# Control.net
KiCad netlist of a schematic drawn in Altium Designer
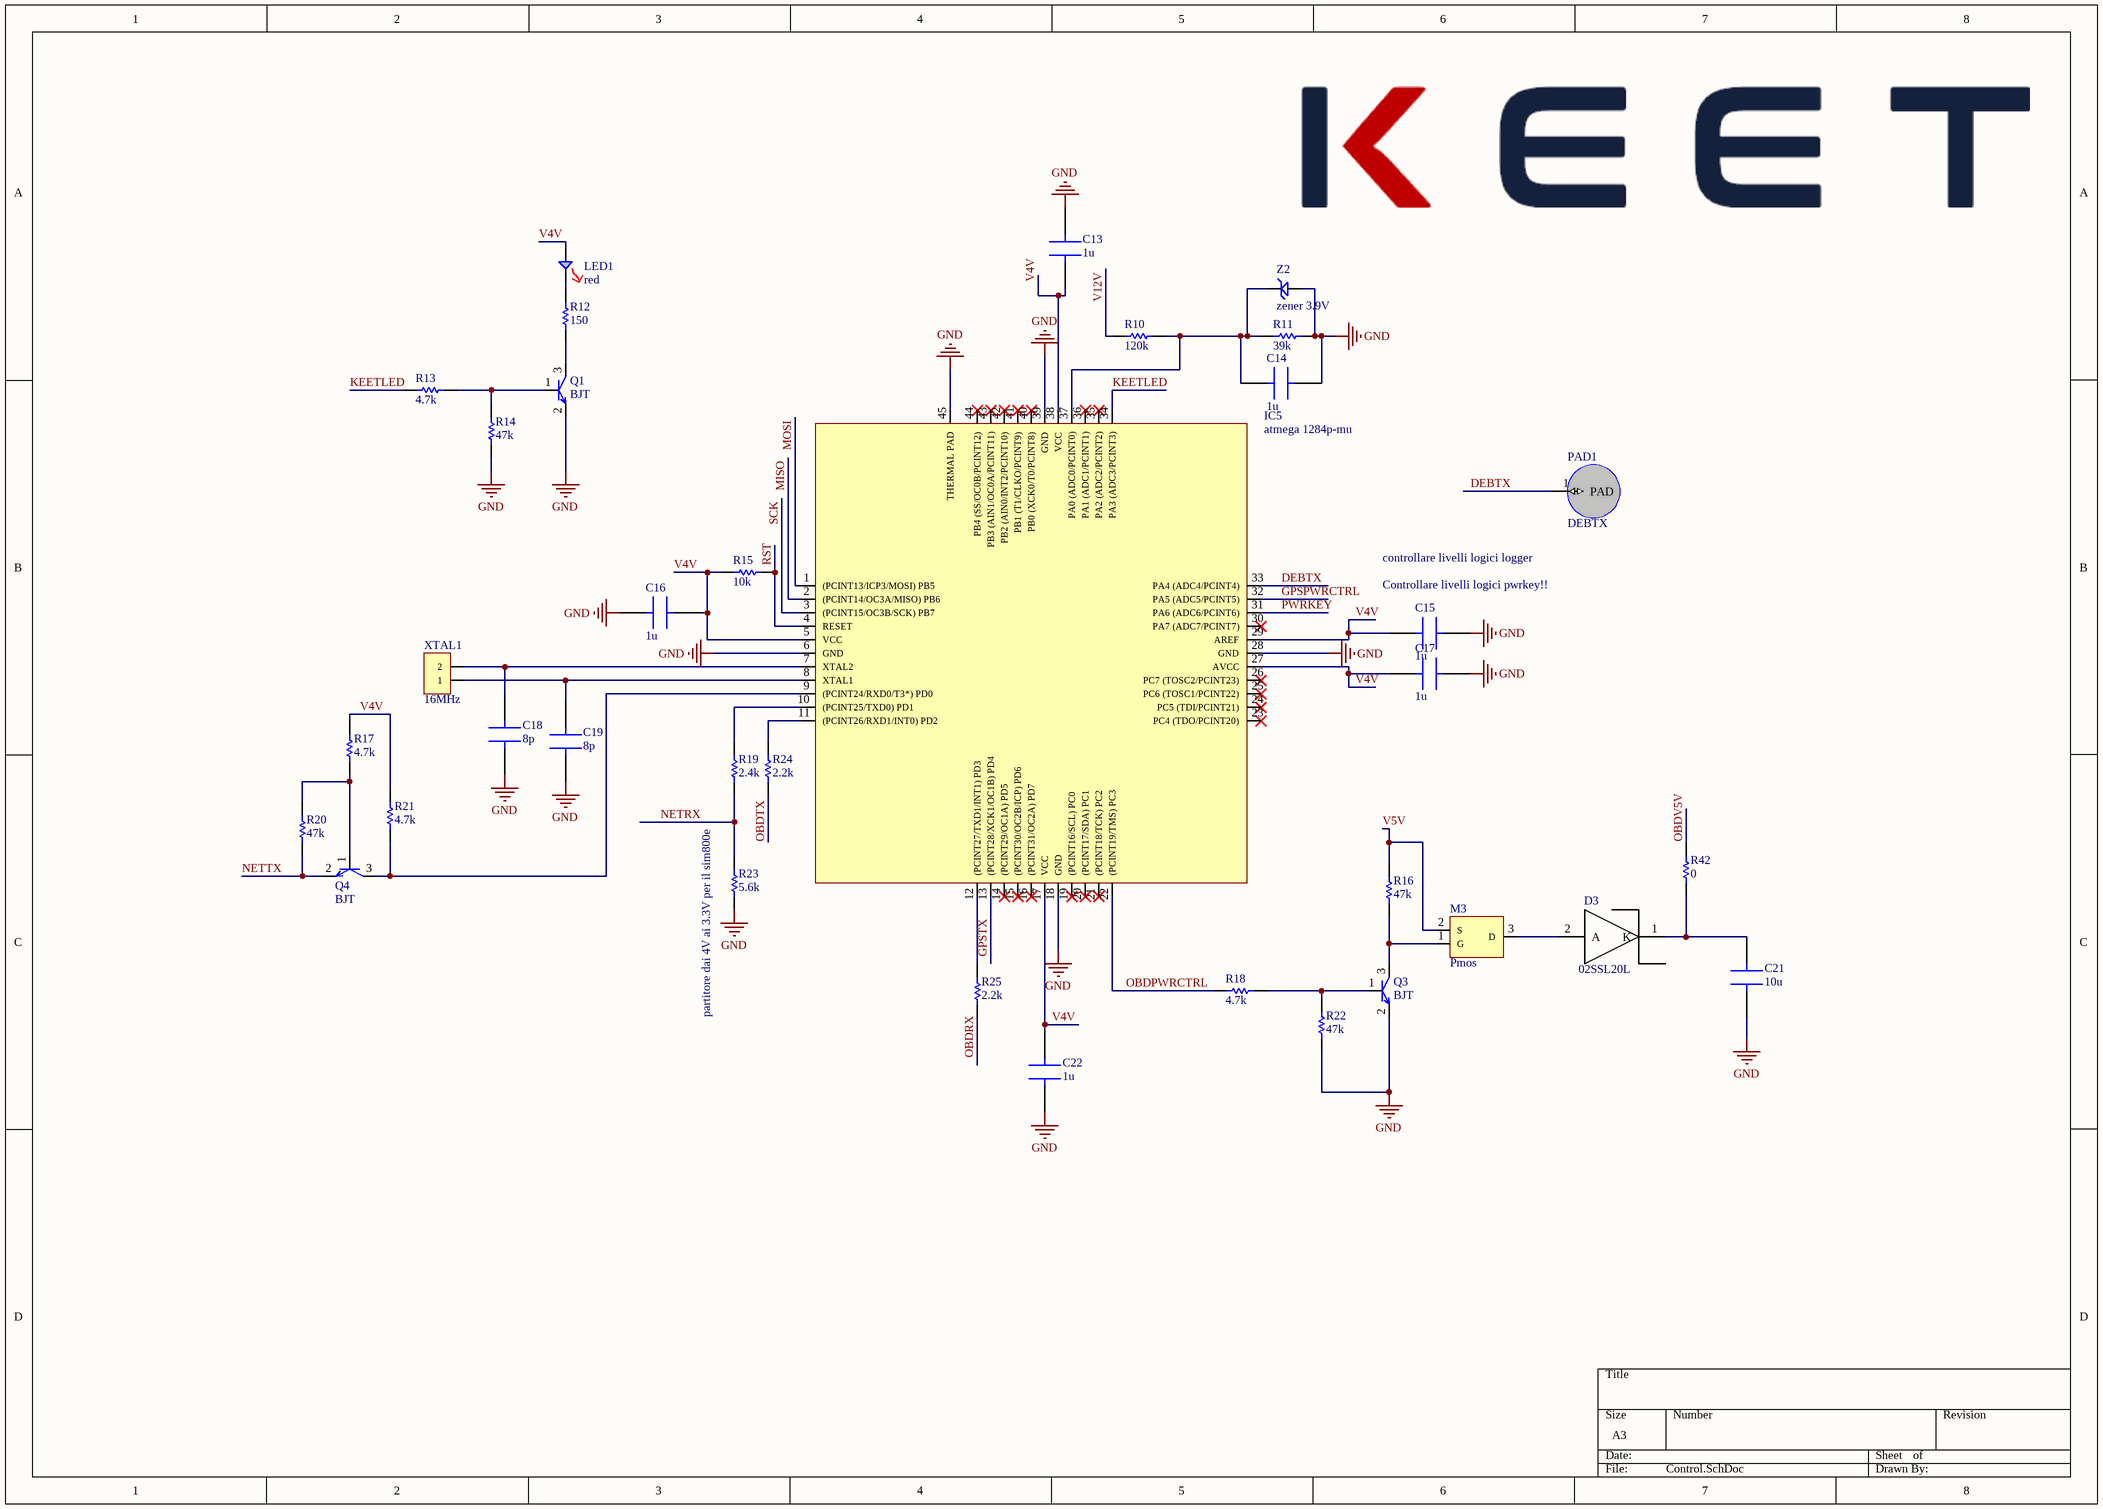
[diagram p0: Control.SchDoc]

(export (version "E")
  (design (tool "Eeschema 10.0.6"))
  (components
    (comp (ref "C13")
      (value "1u")
      (footprint "CAPC1005X06N")
      (description "TAIYO YUDEN - EMK105BJ105KVHF - CAPACITOR,CERAMIC,0402,16V,X5R,1 F, 10% ROHS COMPLIANT: YES")
      (fields
        (field (name "MANUFACTURER") "Taiyo Yuden")
        (field (name "MANUFACTURER PART NUMBER") "EMK105BJ105KVHF")
      )
      (libsource (lib "KeetV2") (part "EMK105BJ105KVHF"))
    )
    (comp (ref "C14")
      (value "1u")
      (footprint "CAPC1005X06N")
      (description "TAIYO YUDEN - EMK105BJ105KVHF - CAPACITOR,CERAMIC,0402,16V,X5R,1 F, 10% ROHS COMPLIANT: YES")
      (fields
        (field (name "MANUFACTURER") "Taiyo Yuden")
        (field (name "MANUFACTURER PART NUMBER") "EMK105BJ105KVHF")
      )
      (libsource (lib "KeetV2") (part "EMK105BJ105KVHF"))
    )
    (comp (ref "C15")
      (value "1u")
      (footprint "CAPC1005X06N")
      (description "TAIYO YUDEN - EMK105BJ105KVHF - CAPACITOR,CERAMIC,0402,16V,X5R,1 F, 10% ROHS COMPLIANT: YES")
      (fields
        (field (name "MANUFACTURER") "Taiyo Yuden")
        (field (name "MANUFACTURER PART NUMBER") "EMK105BJ105KVHF")
      )
      (libsource (lib "KeetV2") (part "EMK105BJ105KVHF"))
    )
    (comp (ref "C16")
      (value "1u")
      (footprint "CAPC1005X06N")
      (description "TAIYO YUDEN - EMK105BJ105KVHF - CAPACITOR,CERAMIC,0402,16V,X5R,1 F, 10% ROHS COMPLIANT: YES")
      (fields
        (field (name "MANUFACTURER") "Taiyo Yuden")
        (field (name "MANUFACTURER PART NUMBER") "EMK105BJ105KVHF")
      )
      (libsource (lib "KeetV2") (part "EMK105BJ105KVHF"))
    )
    (comp (ref "C17")
      (value "1u")
      (footprint "CAPC1005X06N")
      (description "TAIYO YUDEN - EMK105BJ105KVHF - CAPACITOR,CERAMIC,0402,16V,X5R,1 F, 10% ROHS COMPLIANT: YES")
      (fields
        (field (name "MANUFACTURER") "Taiyo Yuden")
        (field (name "MANUFACTURER PART NUMBER") "EMK105BJ105KVHF")
      )
      (libsource (lib "KeetV2") (part "EMK105BJ105KVHF"))
    )
    (comp (ref "C18")
      (value "8p")
      (footprint "CAPC1005X06N")
      (description "Cap Ceramic 8pF 50V C0G 1% SMD 0402 125C Paper T/R")
      (fields
        (field (name "MANUFACTURER") "Murata")
        (field (name "MANUFACTURER PART NUMBER") "GCM1555C1H8R0FA16D")
      )
      (libsource (lib "KeetV2") (part "GCM1555C1H8R0FA16D"))
    )
    (comp (ref "C19")
      (value "8p")
      (footprint "CAPC1005X06N")
      (description "Cap Ceramic 8pF 50V C0G 1% SMD 0402 125C Paper T/R")
      (fields
        (field (name "MANUFACTURER") "Murata")
        (field (name "MANUFACTURER PART NUMBER") "GCM1555C1H8R0FA16D")
      )
      (libsource (lib "KeetV2") (part "GCM1555C1H8R0FA16D"))
    )
    (comp (ref "C21")
      (value "10u")
      (footprint "CAPC1608X10N")
      (fields
        (field (name "MANUFACTURER") "TDK")
        (field (name "MANUFACTURER PART NUMBER") "C1608X5R1A106K080AC")
        (field (name "TOLERANCE") "10%")
      )
      (libsource (lib "KeetV2") (part "C1608X5R1A106K080AC"))
    )
    (comp (ref "C22")
      (value "1u")
      (footprint "CAPC1005X06N")
      (description "TAIYO YUDEN - EMK105BJ105KVHF - CAPACITOR,CERAMIC,0402,16V,X5R,1 F, 10% ROHS COMPLIANT: YES")
      (fields
        (field (name "MANUFACTURER") "Taiyo Yuden")
        (field (name "MANUFACTURER PART NUMBER") "EMK105BJ105KVHF")
      )
      (libsource (lib "KeetV2") (part "EMK105BJ105KVHF"))
    )
    (comp (ref "D3")
      (value "02SSL20L")
      (footprint "SODFL370X100-2N")
      (description "SCHOTTKY DIODE https://eu.mouser.com/datasheet/2/345/02ssl20l-02ssl40l-1107799.pdf")
      (libsource (lib "KeetV2") (part "02SSL20L"))
    )
    (comp (ref "IC5")
      (value "atmega 1284p-mu")
      (footprint "QFN50P700X700X100_HS-45N")
      (description "MCU 8-bit ATmega AVR RISC 128KB Flash 2.5V/3.3V/5V 44-Pin VQFN EP")
      (fields
        (field (name "MANUFACTURER") "Microchip / Atmel")
        (field (name "MANUFACTURER PART NUMBER") "ATMEGA1284P-MU")
      )
      (libsource (lib "KeetV2") (part "ATMEGA1284P-MU"))
    )
    (comp (ref "LED1")
      (value "red")
      (footprint "CAC-0P80X160-2N")
      (description "WURTH ELEKTRONIK - 150060RS75000 - LED, Red, 625 nm, 2 V, 30 mA, 250 mcd RoHS Compliant: Yes")
      (fields
        (field (name "MANUFACTURER") "Wurth Electronics")
        (field (name "MANUFACTURER PART NUMBER") "150060RS75000")
      )
      (libsource (lib "KeetV2") (part "150060RS75000"))
    )
    (comp (ref "M3")
      (value "Pmos")
      (footprint "SOT95P245X110-3N")
      (description "P-Channel 12 V 31 mOhm Surface Mount Enhancement Mode Mosfet - SOT-23-3")
      (fields (field (name "MANUFACTURER") "Diodes") (field (name "MANUFACTURER PART NUMBER") "DMP1045U-7"))
      (libsource (lib "KeetV2") (part "DMP1045U-7"))
    )
    (comp (ref "PAD1")
      (value "DEBTX")
      (footprint "PAD")
      (description "just a pad")
      (libsource (lib "Schlib1") (part "PAD"))
    )
    (comp (ref "Q1")
      (value "BJT")
      (footprint "SOT95P245X110-3N")
      (description "ON SEMICONDUCTOR   BC850CLT1G   BIPOLAR TRANSISTOR, NPN, 45V SOT-23")
      (fields
        (field (name "MANUFACTURER") "ON Semiconductor")
        (field (name "MANUFACTURER PART NUMBER") "BC850CLT1G")
      )
      (libsource (lib "KeetV2") (part "BC850CLT1G"))
    )
    (comp (ref "Q3")
      (value "BJT")
      (footprint "SOT95P245X110-3N")
      (description "ON SEMICONDUCTOR   BC850CLT1G   BIPOLAR TRANSISTOR, NPN, 45V SOT-23")
      (fields
        (field (name "MANUFACTURER") "ON Semiconductor")
        (field (name "MANUFACTURER PART NUMBER") "BC850CLT1G")
      )
      (libsource (lib "KeetV2") (part "BC850CLT1G"))
    )
    (comp (ref "Q4")
      (value "BJT")
      (footprint "SOT95P245X110-3N")
      (description "ON SEMICONDUCTOR   BC850CLT1G   BIPOLAR TRANSISTOR, NPN, 45V SOT-23")
      (fields
        (field (name "MANUFACTURER") "ON Semiconductor")
        (field (name "MANUFACTURER PART NUMBER") "BC850CLT1G")
      )
      (libsource (lib "KeetV2") (part "BC850CLT1G"))
    )
    (comp (ref "R10")
      (value "120k")
      (footprint "RESC1005X04N")
      (description "Res Thick Film 0402 120K Ohm 0.5% 0.063W(1/16W) ±100ppm/C Molded SMD Automotive Punched T/R")
      (fields
        (field (name "MANUFACTURER") "Panasonic")
        (field (name "MANUFACTURER PART NUMBER") "ERJ2RKD1203X")
      )
      (libsource (lib "KeetV2") (part "ERJ2RKD1203X"))
    )
    (comp (ref "R11")
      (value "39k")
      (footprint "RESC1005X04N")
      (description "Res Thick Film 0402 39K Ohm 0.5% 0.063W(1/16W) ±50ppm/C Molded SMD Automotive Punched T/R")
      (fields
        (field (name "MANUFACTURER") "Panasonic")
        (field (name "MANUFACTURER PART NUMBER") "ERJ2RHD3902X")
      )
      (libsource (lib "KeetV2") (part "ERJ2RHD3902X"))
    )
    (comp (ref "R12")
      (value "150")
      (footprint "RESC1005X04N")
      (description "RES SMD 150 OHM 1% 1/10W 0402")
      (fields
        (field (name "MANUFACTURER") "Panasonic")
        (field (name "MANUFACTURER PART NUMBER") "ERJ-2RKF1500X")
      )
      (libsource (lib "KeetV2") (part "ERJ-2RKF1500X"))
    )
    (comp (ref "R13")
      (value "4.7k")
      (footprint "RESC1005X04N")
      (description "Res Thick Film 0402 4.7K Ohm 1% 1/10W Â±100ppm/Â°C Molded SMD SMD Punched Carrier T/R")
      (fields
        (field (name "MANUFACTURER") "Panasonic")
        (field (name "MANUFACTURER PART NUMBER") "ERJ-2RKF4701X")
      )
      (libsource (lib "KeetV2") (part "ERJ-2RKF4701X"))
    )
    (comp (ref "R14")
      (value "47k")
      (footprint "RESC1005X04N")
      (description "Resistor;  Thick Film;  47 Kilohms;  0.063 W;  1%;  SMT;  0402;  TCR 37 ppm/DegC")
      (fields
        (field (name "MANUFACTURER") "Vishay")
        (field (name "MANUFACTURER PART NUMBER") "CRCW040247K0FKED")
      )
      (libsource (lib "KeetV2") (part "CRCW040247K0FKED"))
    )
    (comp (ref "R15")
      (value "10k")
      (footprint "RESC1005X04N")
      (description "Res Thick Film 0402 10K Ohm 1% 1/16W ±100ppm/°C Molded SMD Paper T/R")
      (fields
        (field (name "MANUFACTURER") "Vishay")
        (field (name "MANUFACTURER PART NUMBER") "CRCW0402-10K0FKED")
      )
      (libsource (lib "KeetV2") (part "CRCW0402-10K0FKED"))
    )
    (comp (ref "R16")
      (value "47k")
      (footprint "RESC1005X04N")
      (description "Resistor;  Thick Film;  47 Kilohms;  0.063 W;  1%;  SMT;  0402;  TCR 37 ppm/DegC")
      (fields
        (field (name "MANUFACTURER") "Vishay")
        (field (name "MANUFACTURER PART NUMBER") "CRCW040247K0FKED")
      )
      (libsource (lib "KeetV2") (part "CRCW040247K0FKED"))
    )
    (comp (ref "R17")
      (value "4.7k")
      (footprint "RESC1005X04N")
      (description "Res Thick Film 0402 4.7K Ohm 1% 1/10W Â±100ppm/Â°C Molded SMD SMD Punched Carrier T/R")
      (fields
        (field (name "MANUFACTURER") "Panasonic")
        (field (name "MANUFACTURER PART NUMBER") "ERJ-2RKF4701X")
      )
      (libsource (lib "KeetV2") (part "ERJ-2RKF4701X"))
    )
    (comp (ref "R18")
      (value "4.7k")
      (footprint "RESC1005X04N")
      (description "Res Thick Film 0402 4.7K Ohm 1% 1/10W Â±100ppm/Â°C Molded SMD SMD Punched Carrier T/R")
      (fields
        (field (name "MANUFACTURER") "Panasonic")
        (field (name "MANUFACTURER PART NUMBER") "ERJ-2RKF4701X")
      )
      (libsource (lib "KeetV2") (part "ERJ-2RKF4701X"))
    )
    (comp (ref "R19")
      (value "2.4k")
      (footprint "RESC1005X04N")
      (description "Res Thick Film 0402 2.4K Ohm 1% 0.063W(1/16W) ±100ppm/C Epoxy Pad SMD T/R")
      (fields
        (field (name "MANUFACTURER") "Yageo")
        (field (name "MANUFACTURER PART NUMBER") "RC0402FR-072K4L")
      )
      (libsource (lib "KeetV2") (part "RC0402FR-072K4L"))
    )
    (comp (ref "R20")
      (value "47k")
      (footprint "RESC1005X04N")
      (description "Resistor;  Thick Film;  47 Kilohms;  0.063 W;  1%;  SMT;  0402;  TCR 37 ppm/DegC")
      (fields
        (field (name "MANUFACTURER") "Vishay")
        (field (name "MANUFACTURER PART NUMBER") "CRCW040247K0FKED")
      )
      (libsource (lib "KeetV2") (part "CRCW040247K0FKED"))
    )
    (comp (ref "R21")
      (value "4.7k")
      (footprint "RESC1005X04N")
      (description "Res Thick Film 0402 4.7K Ohm 1% 1/10W Â±100ppm/Â°C Molded SMD SMD Punched Carrier T/R")
      (fields
        (field (name "MANUFACTURER") "Panasonic")
        (field (name "MANUFACTURER PART NUMBER") "ERJ-2RKF4701X")
      )
      (libsource (lib "KeetV2") (part "ERJ-2RKF4701X"))
    )
    (comp (ref "R22")
      (value "47k")
      (footprint "RESC1005X04N")
      (description "Resistor;  Thick Film;  47 Kilohms;  0.063 W;  1%;  SMT;  0402;  TCR 37 ppm/DegC")
      (fields
        (field (name "MANUFACTURER") "Vishay")
        (field (name "MANUFACTURER PART NUMBER") "CRCW040247K0FKED")
      )
      (libsource (lib "KeetV2") (part "CRCW040247K0FKED"))
    )
    (comp (ref "R23")
      (value "5.6k")
      (footprint "RESC1005X04N")
      (description "TE Connectivity CRG0402 Series Thick Film Surface Mount Resistor 0402 Case 5.6k 1% 0.063W 100ppm/C")
      (fields
        (field (name "MANUFACTURER") "TE Connectivity")
        (field (name "MANUFACTURER PART NUMBER") "CRG0402F5K6")
      )
      (libsource (lib "KeetV2") (part "CRG0402F5K6"))
    )
    (comp (ref "R24")
      (value "2.2k")
      (footprint "RESC1005X04N")
      (description "Thick Film Resistors - SMD 2.2K OHM 1%")
      (fields
        (field (name "MANUFACTURER") "Yageo")
        (field (name "MANUFACTURER PART NUMBER") "RC0402FR-132K2L")
      )
      (libsource (lib "KeetV2") (part "RC0402FR-132K2L"))
    )
    (comp (ref "R25")
      (value "2.2k")
      (footprint "RESC1005X04N")
      (description "Thick Film Resistors - SMD 2.2K OHM 1%")
      (fields
        (field (name "MANUFACTURER") "Yageo")
        (field (name "MANUFACTURER PART NUMBER") "RC0402FR-132K2L")
      )
      (libsource (lib "KeetV2") (part "RC0402FR-132K2L"))
    )
    (comp (ref "R42")
      (value "0")
      (footprint "RESC1608X04N")
      (description "YAGEO - RC0603JR-130RL - RES, THICK FILM, 0R, 0.1W, 0603")
      (fields
        (field (name "MANUFACTURER") "Yageo")
        (field (name "MANUFACTURER PART NUMBER") "RC0603JR-130RL")
      )
      (libsource (lib "KeetV2") (part "RC0603JR-130RL"))
    )
    (comp (ref "XTAL1")
      (value "16MHz")
      (footprint "DFN145P200X80-2N")
      (description "Crystal 16MHz ±100ppm (Tol) ±100ppm (Stability) 8pF 100Ohm Automotive 2-Pin SMD T/R")
      (fields
        (field (name "MANUFACTURER") "Murata")
        (field (name "MANUFACTURER PART NUMBER") "XRCHA16M000F0A12R0")
      )
      (libsource (lib "KeetV2") (part "XRCHA16M000F0A12R0"))
    )
    (comp (ref "Z2")
      (value "zener 3.9V")
      (footprint "SODFL250X100-2N")
      (description "ON SEMICONDUCTOR - MM3Z3V9ST1G - Zener Single Diode, 3.9 V, 300 mW, SOD-323, 5 %, 2 Pins, 150 °C")
      (fields
        (field (name "MANUFACTURER") "ON Semiconductor")
        (field (name "MANUFACTURER PART NUMBER") "MM3Z3V9ST1G")
      )
      (libsource (lib "KeetV2") (part "MM3Z3V9ST1G"))
    )
  )
  (nets
    (net (code "1") (name "/DEBTX") (class "Default")
      (node (ref "IC5") (pin "33") (pinfunction "PA4_(ADC4/PCINT4)_33") (pintype "passive"))
      (node (ref "PAD1") (pin "1") (pinfunction "PAD_1") (pintype "bidirectional"))
    )
    (net (code "2") (name "/GPSPWRCTRL") (class "Default")
      (node (ref "IC5") (pin "32") (pinfunction "PA5_(ADC5/PCINT5)_32") (pintype "passive"))
    )
    (net (code "3") (name "/GPSTX") (class "Default")
      (node (ref "IC5") (pin "13") (pinfunction "(PCINT28/XCK1/OC1B)_PD4_13") (pintype "passive"))
    )
    (net (code "4") (name "/KEETLED") (class "Default")
      (node (ref "IC5") (pin "34") (pinfunction "PA3_(ADC3/PCINT3)_34") (pintype "passive"))
      (node (ref "R13") (pin "1") (pinfunction "1_1") (pintype "passive"))
    )
    (net (code "5") (name "/MISO") (class "Default")
      (node (ref "IC5") (pin "2") (pinfunction "(PCINT14/OC3A/MISO)_PB6_2") (pintype "passive"))
    )
    (net (code "6") (name "/MOSI") (class "Default")
      (node (ref "IC5") (pin "1") (pinfunction "(PCINT13/ICP3/MOSI)_PB5_1") (pintype "passive"))
    )
    (net (code "7") (name "/NETRX") (class "Default")
      (node (ref "R19") (pin "1") (pinfunction "1_1") (pintype "passive"))
      (node (ref "R23") (pin "2") (pinfunction "2_2") (pintype "passive"))
    )
    (net (code "8") (name "/NETTX") (class "Default")
      (node (ref "Q4") (pin "2") (pinfunction "2_2") (pintype "passive"))
      (node (ref "R20") (pin "1") (pinfunction "1_1") (pintype "passive"))
    )
    (net (code "9") (name "/OBDPWRCTRL") (class "Default")
      (node (ref "IC5") (pin "22") (pinfunction "(PCINT19/TMS)_PC3_22") (pintype "passive"))
      (node (ref "R18") (pin "1") (pinfunction "1_1") (pintype "passive"))
    )
    (net (code "10") (name "/OBDRX") (class "Default")
      (node (ref "R25") (pin "1") (pinfunction "1_1") (pintype "passive"))
    )
    (net (code "11") (name "/OBDTX") (class "Default")
      (node (ref "R24") (pin "1") (pinfunction "1_1") (pintype "passive"))
    )
    (net (code "12") (name "/OBDV5V") (class "Default")
      (node (ref "R42") (pin "2") (pinfunction "2_2") (pintype "passive"))
    )
    (net (code "13") (name "/PWRKEY") (class "Default")
      (node (ref "IC5") (pin "31") (pinfunction "PA6_(ADC6/PCINT6)_31") (pintype "passive"))
    )
    (net (code "14") (name "/RST") (class "Default")
      (node (ref "IC5") (pin "4") (pinfunction "RESET_4") (pintype "passive"))
      (node (ref "R15") (pin "2") (pinfunction "2_2") (pintype "passive"))
    )
    (net (code "15") (name "/SCK") (class "Default")
      (node (ref "IC5") (pin "3") (pinfunction "(PCINT15/OC3B/SCK)_PB7_3") (pintype "passive"))
    )
    (net (code "16") (name "/V4V") (class "Default")
      (node (ref "C13") (pin "1") (pinfunction "1_1") (pintype "passive"))
      (node (ref "C15") (pin "1") (pinfunction "1_1") (pintype "passive"))
      (node (ref "C16") (pin "2") (pinfunction "2_2") (pintype "passive"))
      (node (ref "C17") (pin "1") (pinfunction "1_1") (pintype "passive"))
      (node (ref "C22") (pin "2") (pinfunction "2_2") (pintype "passive"))
      (node (ref "IC5") (pin "17") (pinfunction "VCC_17") (pintype "passive"))
      (node (ref "IC5") (pin "27") (pinfunction "AVCC_27") (pintype "passive"))
      (node (ref "IC5") (pin "29") (pinfunction "AREF_29") (pintype "passive"))
      (node (ref "IC5") (pin "38") (pinfunction "VCC_38") (pintype "passive"))
      (node (ref "IC5") (pin "5") (pinfunction "VCC_5") (pintype "passive"))
      (node (ref "LED1") (pin "2") (pinfunction "2_2") (pintype "passive"))
      (node (ref "R15") (pin "1") (pinfunction "1_1") (pintype "passive"))
      (node (ref "R17") (pin "2") (pinfunction "2_2") (pintype "passive"))
      (node (ref "R21") (pin "2") (pinfunction "2_2") (pintype "passive"))
    )
    (net (code "17") (name "/V5V") (class "Default")
      (node (ref "M3") (pin "2") (pinfunction "S_2") (pintype "passive"))
      (node (ref "R16") (pin "2") (pinfunction "2_2") (pintype "passive"))
    )
    (net (code "18") (name "/V12V") (class "Default")
      (node (ref "R10") (pin "1") (pinfunction "1_1") (pintype "passive"))
    )
    (net (code "19") (name "GND") (class "Default")
      (node (ref "C13") (pin "2") (pinfunction "2_2") (pintype "passive"))
      (node (ref "C14") (pin "2") (pinfunction "2_2") (pintype "passive"))
      (node (ref "C15") (pin "2") (pinfunction "2_2") (pintype "passive"))
      (node (ref "C16") (pin "1") (pinfunction "1_1") (pintype "passive"))
      (node (ref "C17") (pin "2") (pinfunction "2_2") (pintype "passive"))
      (node (ref "C18") (pin "1") (pinfunction "1_1") (pintype "passive"))
      (node (ref "C19") (pin "1") (pinfunction "1_1") (pintype "passive"))
      (node (ref "C21") (pin "1") (pinfunction "1_1") (pintype "passive"))
      (node (ref "C22") (pin "1") (pinfunction "1_1") (pintype "passive"))
      (node (ref "IC5") (pin "18") (pinfunction "GND_18") (pintype "passive"))
      (node (ref "IC5") (pin "28") (pinfunction "GND_28") (pintype "passive"))
      (node (ref "IC5") (pin "39") (pinfunction "GND_39") (pintype "passive"))
      (node (ref "IC5") (pin "45") (pinfunction "THERMAL_PAD_45") (pintype "passive"))
      (node (ref "IC5") (pin "6") (pinfunction "GND_6") (pintype "passive"))
      (node (ref "Q1") (pin "2") (pinfunction "2_2") (pintype "passive"))
      (node (ref "Q3") (pin "2") (pinfunction "2_2") (pintype "passive"))
      (node (ref "R11") (pin "2") (pinfunction "2_2") (pintype "passive"))
      (node (ref "R14") (pin "1") (pinfunction "1_1") (pintype "passive"))
      (node (ref "R22") (pin "1") (pinfunction "1_1") (pintype "passive"))
      (node (ref "R23") (pin "1") (pinfunction "1_1") (pintype "passive"))
      (node (ref "Z2") (pin "2") (pinfunction "2_2") (pintype "passive"))
    )
    (net (code "20") (name "Net-(D3-A)") (class "Default")
      (node (ref "D3") (pin "2") (pinfunction "A_2") (pintype "passive"))
      (node (ref "M3") (pin "3") (pinfunction "D_3") (pintype "passive"))
    )
    (net (code "21") (name "Net-(D3-K)") (class "Default")
      (node (ref "C21") (pin "2") (pinfunction "2_2") (pintype "passive"))
      (node (ref "D3") (pin "1") (pinfunction "K_1") (pintype "passive"))
      (node (ref "R42") (pin "1") (pinfunction "1_1") (pintype "passive"))
    )
    (net (code "22") (name "Net-(IC5-(PCINT24{slash}RXD0{slash}T3*)_PD0)") (class "Default")
      (node (ref "IC5") (pin "9") (pinfunction "(PCINT24/RXD0/T3*)_PD0_9") (pintype "passive"))
      (node (ref "Q4") (pin "3") (pinfunction "3_3") (pintype "passive"))
      (node (ref "R21") (pin "1") (pinfunction "1_1") (pintype "passive"))
    )
    (net (code "23") (name "Net-(IC5-(PCINT25{slash}TXD0)_PD1)") (class "Default")
      (node (ref "IC5") (pin "10") (pinfunction "(PCINT25/TXD0)_PD1_10") (pintype "passive"))
      (node (ref "R19") (pin "2") (pinfunction "2_2") (pintype "passive"))
    )
    (net (code "24") (name "Net-(IC5-(PCINT26{slash}RXD1{slash}INT0)_PD2)") (class "Default")
      (node (ref "IC5") (pin "11") (pinfunction "(PCINT26/RXD1/INT0)_PD2_11") (pintype "passive"))
      (node (ref "R24") (pin "2") (pinfunction "2_2") (pintype "passive"))
    )
    (net (code "25") (name "Net-(IC5-(PCINT27{slash}TXD1{slash}INT1)_PD3)") (class "Default")
      (node (ref "IC5") (pin "12") (pinfunction "(PCINT27/TXD1/INT1)_PD3_12") (pintype "passive"))
      (node (ref "R25") (pin "2") (pinfunction "2_2") (pintype "passive"))
    )
    (net (code "26") (name "Net-(IC5-PA0_(ADC0{slash}PCINT0))") (class "Default")
      (node (ref "C14") (pin "1") (pinfunction "1_1") (pintype "passive"))
      (node (ref "IC5") (pin "37") (pinfunction "PA0_(ADC0/PCINT0)_37") (pintype "passive"))
      (node (ref "R10") (pin "2") (pinfunction "2_2") (pintype "passive"))
      (node (ref "R11") (pin "1") (pinfunction "1_1") (pintype "passive"))
      (node (ref "Z2") (pin "1") (pinfunction "1_1") (pintype "passive"))
    )
    (net (code "27") (name "Net-(IC5-XTAL1)") (class "Default")
      (node (ref "C19") (pin "2") (pinfunction "2_2") (pintype "passive"))
      (node (ref "IC5") (pin "8") (pinfunction "XTAL1_8") (pintype "passive"))
      (node (ref "XTAL1") (pin "1") (pinfunction "1_1") (pintype "passive"))
    )
    (net (code "28") (name "Net-(IC5-XTAL2)") (class "Default")
      (node (ref "C18") (pin "2") (pinfunction "2_2") (pintype "passive"))
      (node (ref "IC5") (pin "7") (pinfunction "XTAL2_7") (pintype "passive"))
      (node (ref "XTAL1") (pin "2") (pinfunction "2_2") (pintype "passive"))
    )
    (net (code "29") (name "Net-(LED1-Pad1)") (class "Default")
      (node (ref "LED1") (pin "1") (pinfunction "1_1") (pintype "passive"))
      (node (ref "R12") (pin "2") (pinfunction "2_2") (pintype "passive"))
    )
    (net (code "30") (name "Net-(M3-G)") (class "Default")
      (node (ref "M3") (pin "1") (pinfunction "G_1") (pintype "passive"))
      (node (ref "Q3") (pin "3") (pinfunction "3_3") (pintype "passive"))
      (node (ref "R16") (pin "1") (pinfunction "1_1") (pintype "passive"))
    )
    (net (code "31") (name "Net-(Q1-Pad1)") (class "Default")
      (node (ref "Q1") (pin "1") (pinfunction "1_1") (pintype "passive"))
      (node (ref "R13") (pin "2") (pinfunction "2_2") (pintype "passive"))
      (node (ref "R14") (pin "2") (pinfunction "2_2") (pintype "passive"))
    )
    (net (code "32") (name "Net-(Q1-Pad3)") (class "Default")
      (node (ref "Q1") (pin "3") (pinfunction "3_3") (pintype "passive"))
      (node (ref "R12") (pin "1") (pinfunction "1_1") (pintype "passive"))
    )
    (net (code "33") (name "Net-(Q3-Pad1)") (class "Default")
      (node (ref "Q3") (pin "1") (pinfunction "1_1") (pintype "passive"))
      (node (ref "R18") (pin "2") (pinfunction "2_2") (pintype "passive"))
      (node (ref "R22") (pin "2") (pinfunction "2_2") (pintype "passive"))
    )
    (net (code "34") (name "Net-(Q4-Pad1)") (class "Default")
      (node (ref "Q4") (pin "1") (pinfunction "1_1") (pintype "passive"))
      (node (ref "R17") (pin "1") (pinfunction "1_1") (pintype "passive"))
      (node (ref "R20") (pin "2") (pinfunction "2_2") (pintype "passive"))
    )
    (net (code "35") (name "unconnected-(IC5-(PCINT16{slash}SCL)_PC0-Pad19)") (class "Default")
      (node (ref "IC5") (pin "19") (pinfunction "(PCINT16/SCL)_PC0_19") (pintype "passive+no_connect"))
    )
    (net (code "36") (name "unconnected-(IC5-(PCINT17{slash}SDA)_PC1-Pad20)") (class "Default")
      (node (ref "IC5") (pin "20") (pinfunction "(PCINT17/SDA)_PC1_20") (pintype "passive+no_connect"))
    )
    (net (code "37") (name "unconnected-(IC5-(PCINT18{slash}TCK)_PC2-Pad21)") (class "Default")
      (node (ref "IC5") (pin "21") (pinfunction "(PCINT18/TCK)_PC2_21") (pintype "passive+no_connect"))
    )
    (net (code "38") (name "unconnected-(IC5-(PCINT29{slash}OC1A)_PD5-Pad14)") (class "Default")
      (node (ref "IC5") (pin "14") (pinfunction "(PCINT29/OC1A)_PD5_14") (pintype "passive+no_connect"))
    )
    (net (code "39") (name "unconnected-(IC5-(PCINT30{slash}OC2B{slash}ICP)_PD6-Pad15)") (class "Default")
      (node (ref "IC5") (pin "15") (pinfunction "(PCINT30/OC2B/ICP)_PD6_15") (pintype "passive+no_connect"))
    )
    (net (code "40") (name "unconnected-(IC5-(PCINT31{slash}OC2A)_PD7-Pad16)") (class "Default")
      (node (ref "IC5") (pin "16") (pinfunction "(PCINT31/OC2A)_PD7_16") (pintype "passive+no_connect"))
    )
    (net (code "41") (name "unconnected-(IC5-PA1_(ADC1{slash}PCINT1)-Pad36)") (class "Default")
      (node (ref "IC5") (pin "36") (pinfunction "PA1_(ADC1/PCINT1)_36") (pintype "passive+no_connect"))
    )
    (net (code "42") (name "unconnected-(IC5-PA2_(ADC2{slash}PCINT2)-Pad35)") (class "Default")
      (node (ref "IC5") (pin "35") (pinfunction "PA2_(ADC2/PCINT2)_35") (pintype "passive+no_connect"))
    )
    (net (code "43") (name "unconnected-(IC5-PA7_(ADC7{slash}PCINT7)-Pad30)") (class "Default")
      (node (ref "IC5") (pin "30") (pinfunction "PA7_(ADC7/PCINT7)_30") (pintype "passive+no_connect"))
    )
    (net (code "44") (name "unconnected-(IC5-PB0_(XCK0{slash}T0{slash}PCINT8)-Pad40)") (class "Default")
      (node (ref "IC5") (pin "40") (pinfunction "PB0_(XCK0/T0/PCINT8)_40") (pintype "passive+no_connect"))
    )
    (net (code "45") (name "unconnected-(IC5-PB1_(T1{slash}CLKO{slash}PCINT9)-Pad41)") (class "Default")
      (node (ref "IC5") (pin "41") (pinfunction "PB1_(T1/CLKO/PCINT9)_41") (pintype "passive+no_connect"))
    )
    (net (code "46") (name "unconnected-(IC5-PB2_(AIN0{slash}INT2{slash}PCINT10)-Pad42)") (class "Default")
      (node (ref "IC5") (pin "42") (pinfunction "PB2_(AIN0/INT2/PCINT10)_42") (pintype "passive+no_connect"))
    )
    (net (code "47") (name "unconnected-(IC5-PB3_(AIN1{slash}OC0A{slash}PCINT11)-Pad43)") (class "Default")
      (node (ref "IC5") (pin "43") (pinfunction "PB3_(AIN1/OC0A/PCINT11)_43") (pintype "passive+no_connect"))
    )
    (net (code "48") (name "unconnected-(IC5-PB4_(SS{slash}OC0B{slash}PCINT12)-Pad44)") (class "Default")
      (node (ref "IC5") (pin "44") (pinfunction "PB4_(SS/OC0B/PCINT12)_44") (pintype "passive+no_connect"))
    )
    (net (code "49") (name "unconnected-(IC5-PC4_(TDO{slash}PCINT20)-Pad23)") (class "Default")
      (node (ref "IC5") (pin "23") (pinfunction "PC4_(TDO/PCINT20)_23") (pintype "passive+no_connect"))
    )
    (net (code "50") (name "unconnected-(IC5-PC5_(TDI{slash}PCINT21)-Pad24)") (class "Default")
      (node (ref "IC5") (pin "24") (pinfunction "PC5_(TDI/PCINT21)_24") (pintype "passive+no_connect"))
    )
    (net (code "51") (name "unconnected-(IC5-PC6_(TOSC1{slash}PCINT22)-Pad25)") (class "Default")
      (node (ref "IC5") (pin "25") (pinfunction "PC6_(TOSC1/PCINT22)_25") (pintype "passive+no_connect"))
    )
    (net (code "52") (name "unconnected-(IC5-PC7_(TOSC2{slash}PCINT23)-Pad26)") (class "Default")
      (node (ref "IC5") (pin "26") (pinfunction "PC7_(TOSC2/PCINT23)_26") (pintype "passive+no_connect"))
    )
  )
)
